# rfm69-spi.net
KiCad netlist of a schematic drawn in EAGLE
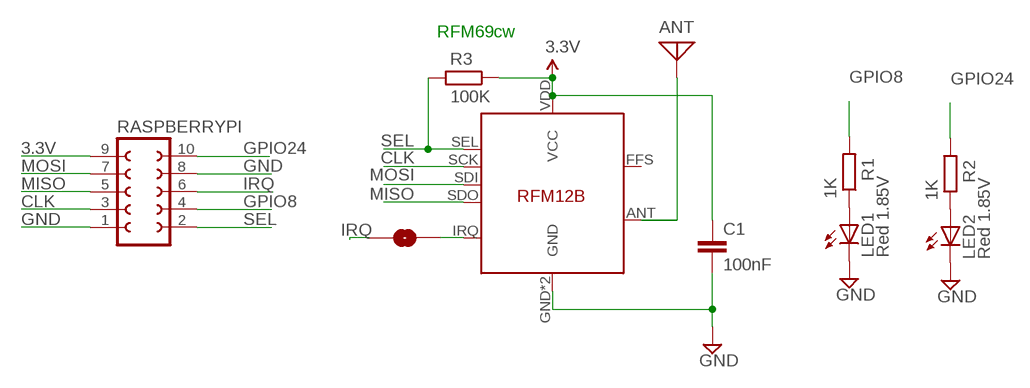
[diagram p0: schematic, sheet 1]

(export (version "E")
  (design (tool "Eeschema 10.0.6"))
  (components
    (comp (ref "ANT")
      (value "ANTENNA")
      (footprint "eagle-import:PAD-01")
      (libsource (lib "eagle-import") (part "ANTENNA"))
    )
    (comp (ref "C1")
      (value "100nF")
      (footprint "eagle-import:C0603")
      (libsource (lib "eagle-import") (part "C-EUC0603"))
    )
    (comp (ref "GPIO15")
      (value "SOLDERJUMPERNO")
      (footprint "eagle-import:SJ_2S-NO")
      (libsource (lib "eagle-import") (part "SOLDERJUMPERNO"))
    )
    (comp (ref "LED1")
      (value "Red 1.85V")
      (footprint "eagle-import:CHIP-LED0805")
      (libsource (lib "eagle-import") (part "LEDCHIP-LED0805"))
    )
    (comp (ref "LED2")
      (value "Red 1.85V")
      (footprint "eagle-import:CHIP-LED0805")
      (libsource (lib "eagle-import") (part "LEDCHIP-LED0805"))
    )
    (comp (ref "R1")
      (value "1K")
      (footprint "eagle-import:R0603")
      (libsource (lib "eagle-import") (part "R-EU_R0603"))
    )
    (comp (ref "R2")
      (value "1K")
      (footprint "eagle-import:R0603")
      (libsource (lib "eagle-import") (part "R-EU_R0603"))
    )
    (comp (ref "R3")
      (value "100K")
      (footprint "eagle-import:R0603")
      (libsource (lib "eagle-import") (part "R-EU_R0603"))
    )
    (comp (ref "RASPBERRYPI")
      (value "FE05-2")
      (footprint "eagle-import:FE05-2")
      (libsource (lib "eagle-import") (part "FE05-2"))
    )
    (comp (ref "U$14")
      (value "RFM12B")
      (footprint "eagle-import:RFM12B")
      (libsource (lib "eagle-import") (part "RFM12B"))
    )
  )
  (nets
    (net (code "1") (name "/CLK") (class "Default")
      (node (ref "RASPBERRYPI") (pin "3") (pinfunction "3_3") (pintype "passive"))
      (node (ref "U$14") (pin "SCK") (pinfunction "SCK_SCK") (pintype "input"))
    )
    (net (code "2") (name "/GPIO8") (class "Default")
      (node (ref "R1") (pin "2") (pinfunction "2_2") (pintype "passive"))
      (node (ref "RASPBERRYPI") (pin "4") (pinfunction "4_4") (pintype "passive"))
    )
    (net (code "3") (name "/GPIO24") (class "Default")
      (node (ref "R2") (pin "2") (pinfunction "2_2") (pintype "passive"))
      (node (ref "RASPBERRYPI") (pin "10") (pinfunction "10_10") (pintype "passive"))
    )
    (net (code "4") (name "/IRQ") (class "Default")
      (node (ref "GPIO15") (pin "2") (pinfunction "2_2") (pintype "passive"))
      (node (ref "RASPBERRYPI") (pin "6") (pinfunction "6_6") (pintype "passive"))
    )
    (net (code "5") (name "/MISO") (class "Default")
      (node (ref "RASPBERRYPI") (pin "5") (pinfunction "5_5") (pintype "passive"))
      (node (ref "U$14") (pin "SDO") (pinfunction "SDO_SDO") (pintype "output"))
    )
    (net (code "6") (name "/MOSI") (class "Default")
      (node (ref "RASPBERRYPI") (pin "7") (pinfunction "7_7") (pintype "passive"))
      (node (ref "U$14") (pin "SDI") (pinfunction "SDI_SDI") (pintype "input"))
    )
    (net (code "7") (name "/SEL") (class "Default")
      (node (ref "R3") (pin "2") (pinfunction "2_2") (pintype "passive"))
      (node (ref "RASPBERRYPI") (pin "2") (pinfunction "2_2") (pintype "passive"))
      (node (ref "U$14") (pin "SEL") (pinfunction "SEL_SEL") (pintype "input"))
    )
    (net (code "8") (name "3.3V") (class "Default")
      (node (ref "C1") (pin "1") (pinfunction "1_1") (pintype "passive"))
      (node (ref "R3") (pin "1") (pinfunction "1_1") (pintype "passive"))
      (node (ref "RASPBERRYPI") (pin "9") (pinfunction "9_9") (pintype "passive"))
      (node (ref "U$14") (pin "VDD") (pinfunction "VCC_VDD") (pintype "power_in"))
    )
    (net (code "9") (name "GND") (class "Default")
      (node (ref "C1") (pin "2") (pinfunction "2_2") (pintype "passive"))
      (node (ref "LED1") (pin "C") (pinfunction "C_C") (pintype "passive"))
      (node (ref "LED2") (pin "C") (pinfunction "C_C") (pintype "passive"))
      (node (ref "RASPBERRYPI") (pin "1") (pinfunction "1_1") (pintype "passive"))
      (node (ref "RASPBERRYPI") (pin "8") (pinfunction "8_8") (pintype "passive"))
      (node (ref "U$14") (pin "GND") (pinfunction "GND_GND") (pintype "power_in"))
      (node (ref "U$14") (pin "P$12") (pinfunction "GND_P$12") (pintype "power_in"))
    )
    (net (code "10") (name "Net-(ANT-Pad1)") (class "Default")
      (node (ref "ANT") (pin "1") (pinfunction "1_1") (pintype "output"))
      (node (ref "U$14") (pin "ANT") (pinfunction "ANT_ANT") (pintype "passive"))
    )
    (net (code "11") (name "Net-(GPIO15-Pad1)") (class "Default")
      (node (ref "GPIO15") (pin "1") (pinfunction "1_1") (pintype "passive"))
      (node (ref "U$14") (pin "IRQ") (pinfunction "IRQ_IRQ") (pintype "open_collector"))
    )
    (net (code "12") (name "Net-(LED1-PadA)") (class "Default")
      (node (ref "LED1") (pin "A") (pinfunction "A_A") (pintype "passive"))
      (node (ref "R1") (pin "1") (pinfunction "1_1") (pintype "passive"))
    )
    (net (code "13") (name "Net-(LED2-PadA)") (class "Default")
      (node (ref "LED2") (pin "A") (pinfunction "A_A") (pintype "passive"))
      (node (ref "R2") (pin "1") (pinfunction "1_1") (pintype "passive"))
    )
    (net (code "14") (name "unconnected-(U$14-PadFFS)") (class "Default")
      (node (ref "U$14") (pin "FFS") (pinfunction "FFS_FFS") (pintype "bidirectional"))
    )
  )
)
